# MATRIX_SCH.net
KiCad netlist of a schematic drawn in Altium Designer
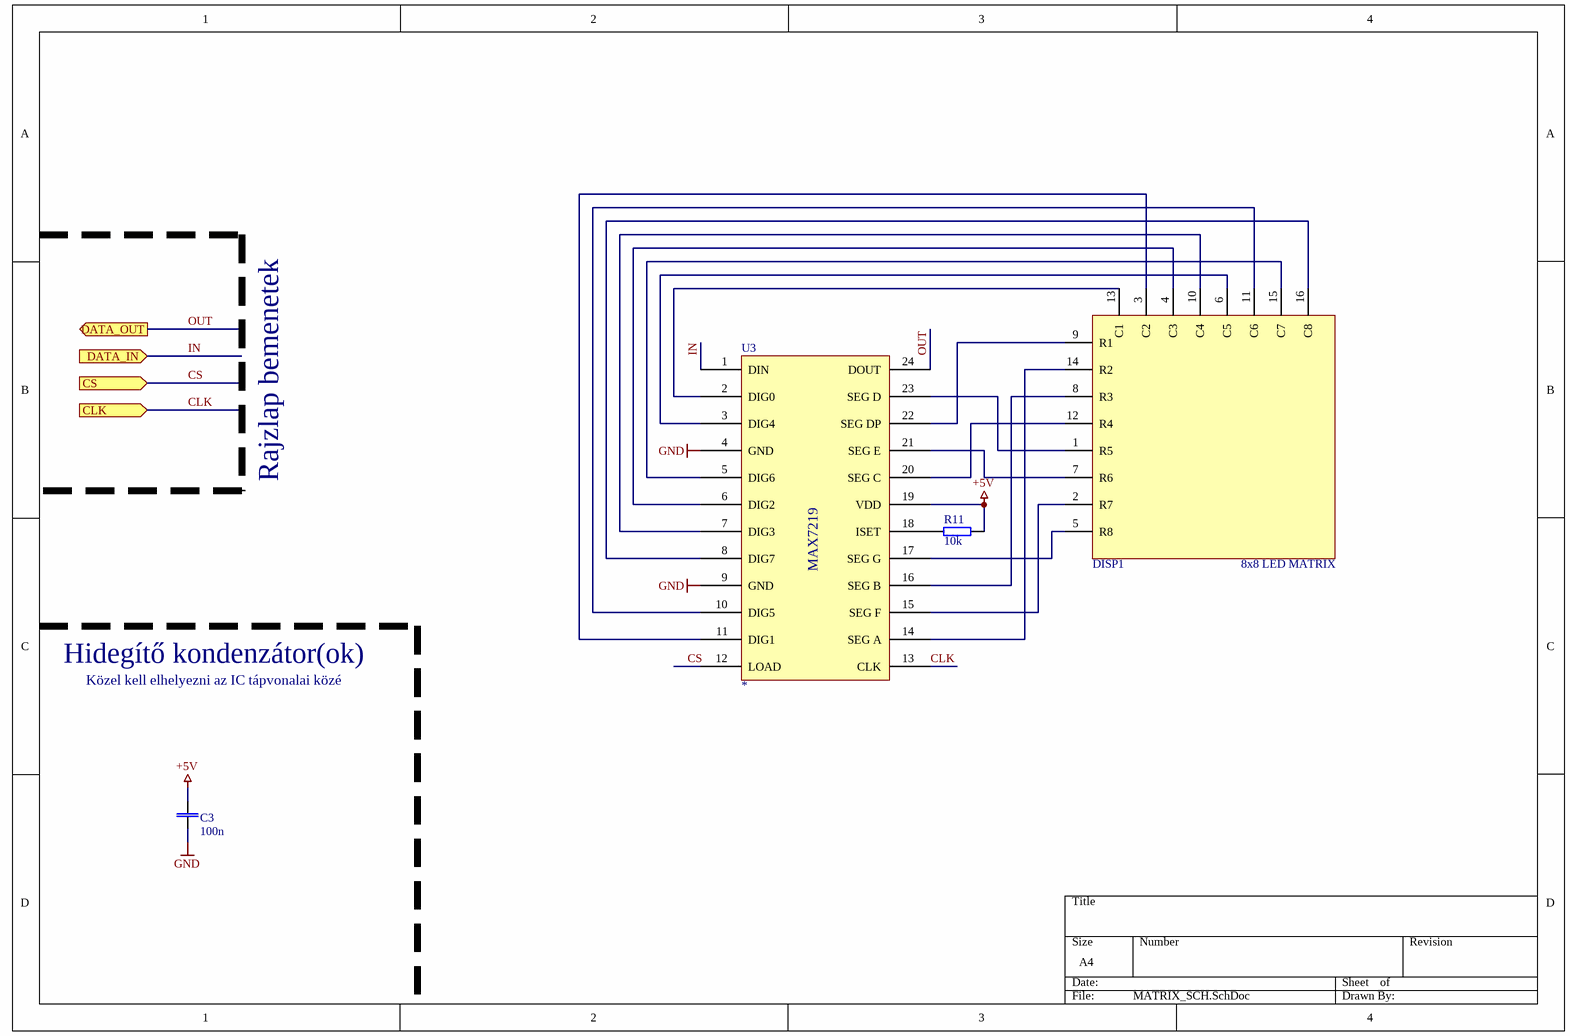
[diagram p0: MATRIX_SCH.SchDoc]

(export (version "E")
  (design (tool "Eeschema 10.0.6"))
  (components
    (comp (ref "C3")
      (value "100n")
      (footprint "CAP 0805")
      (description "NON POLARIZED CAPACITOR")
      (libsource (lib "SCH_LIB") (part "CAP"))
    )
    (comp (ref "DISP1")
      (value "8x8 LED MATRIX")
      (footprint "8x8_32mm_LED_MATRIX")
      (description "8x8 LED Matrix display")
      (libsource (lib "SCH_LIB") (part "8x8_LED_MATRIX"))
    )
    (comp (ref "R11")
      (value "10k")
      (footprint "RES 0805")
      (description "RESISTOR")
      (libsource (lib "SCH_LIB") (part "RES"))
    )
    (comp (ref "U3")
      (value "*")
      (footprint "SO24")
      (description "8X8 LED DRIVER IC")
      (libsource (lib "SCH_LIB") (part "MAX7219"))
    )
  )
  (nets
    (net (code "1") (name "+5V") (class "Default")
      (node (ref "C3") (pin "2") (pinfunction "2_2") (pintype "passive"))
      (node (ref "R11") (pin "2") (pinfunction "2_2") (pintype "passive"))
      (node (ref "U3") (pin "19") (pinfunction "VDD_19") (pintype "passive"))
    )
    (net (code "2") (name "/CLK") (class "Default")
      (node (ref "U3") (pin "13") (pinfunction "CLK_13") (pintype "passive"))
    )
    (net (code "3") (name "/CS") (class "Default")
      (node (ref "U3") (pin "12") (pinfunction "LOAD_12") (pintype "passive"))
    )
    (net (code "4") (name "/IN") (class "Default")
      (node (ref "U3") (pin "1") (pinfunction "DIN_1") (pintype "passive"))
    )
    (net (code "5") (name "/OUT") (class "Default")
      (node (ref "U3") (pin "24") (pinfunction "DOUT_24") (pintype "passive"))
    )
    (net (code "6") (name "GND") (class "Default")
      (node (ref "C3") (pin "1") (pinfunction "1_1") (pintype "passive"))
      (node (ref "U3") (pin "4") (pinfunction "GND_4") (pintype "passive"))
      (node (ref "U3") (pin "9") (pinfunction "GND_9") (pintype "passive"))
    )
    (net (code "7") (name "Net-(DISP1-C1)") (class "Default")
      (node (ref "DISP1") (pin "13") (pinfunction "C1_13") (pintype "passive"))
      (node (ref "U3") (pin "2") (pinfunction "DIG0_2") (pintype "passive"))
    )
    (net (code "8") (name "Net-(DISP1-C2)") (class "Default")
      (node (ref "DISP1") (pin "3") (pinfunction "C2_3") (pintype "passive"))
      (node (ref "U3") (pin "11") (pinfunction "DIG1_11") (pintype "passive"))
    )
    (net (code "9") (name "Net-(DISP1-C3)") (class "Default")
      (node (ref "DISP1") (pin "4") (pinfunction "C3_4") (pintype "passive"))
      (node (ref "U3") (pin "6") (pinfunction "DIG2_6") (pintype "passive"))
    )
    (net (code "10") (name "Net-(DISP1-C4)") (class "Default")
      (node (ref "DISP1") (pin "10") (pinfunction "C4_10") (pintype "passive"))
      (node (ref "U3") (pin "7") (pinfunction "DIG3_7") (pintype "passive"))
    )
    (net (code "11") (name "Net-(DISP1-C5)") (class "Default")
      (node (ref "DISP1") (pin "6") (pinfunction "C5_6") (pintype "passive"))
      (node (ref "U3") (pin "3") (pinfunction "DIG4_3") (pintype "passive"))
    )
    (net (code "12") (name "Net-(DISP1-C6)") (class "Default")
      (node (ref "DISP1") (pin "11") (pinfunction "C6_11") (pintype "passive"))
      (node (ref "U3") (pin "10") (pinfunction "DIG5_10") (pintype "passive"))
    )
    (net (code "13") (name "Net-(DISP1-C7)") (class "Default")
      (node (ref "DISP1") (pin "15") (pinfunction "C7_15") (pintype "passive"))
      (node (ref "U3") (pin "5") (pinfunction "DIG6_5") (pintype "passive"))
    )
    (net (code "14") (name "Net-(DISP1-C8)") (class "Default")
      (node (ref "DISP1") (pin "16") (pinfunction "C8_16") (pintype "passive"))
      (node (ref "U3") (pin "8") (pinfunction "DIG7_8") (pintype "passive"))
    )
    (net (code "15") (name "Net-(DISP1-R1)") (class "Default")
      (node (ref "DISP1") (pin "9") (pinfunction "R1_9") (pintype "passive"))
      (node (ref "U3") (pin "22") (pinfunction "SEG_DP_22") (pintype "passive"))
    )
    (net (code "16") (name "Net-(DISP1-R2)") (class "Default")
      (node (ref "DISP1") (pin "14") (pinfunction "R2_14") (pintype "passive"))
      (node (ref "U3") (pin "14") (pinfunction "SEG_A_14") (pintype "passive"))
    )
    (net (code "17") (name "Net-(DISP1-R3)") (class "Default")
      (node (ref "DISP1") (pin "8") (pinfunction "R3_8") (pintype "passive"))
      (node (ref "U3") (pin "16") (pinfunction "SEG_B_16") (pintype "passive"))
    )
    (net (code "18") (name "Net-(DISP1-R4)") (class "Default")
      (node (ref "DISP1") (pin "12") (pinfunction "R4_12") (pintype "passive"))
      (node (ref "U3") (pin "20") (pinfunction "SEG_C_20") (pintype "passive"))
    )
    (net (code "19") (name "Net-(DISP1-R5)") (class "Default")
      (node (ref "DISP1") (pin "1") (pinfunction "R5_1") (pintype "passive"))
      (node (ref "U3") (pin "23") (pinfunction "SEG_D_23") (pintype "passive"))
    )
    (net (code "20") (name "Net-(DISP1-R6)") (class "Default")
      (node (ref "DISP1") (pin "7") (pinfunction "R6_7") (pintype "passive"))
      (node (ref "U3") (pin "21") (pinfunction "SEG_E_21") (pintype "passive"))
    )
    (net (code "21") (name "Net-(DISP1-R7)") (class "Default")
      (node (ref "DISP1") (pin "2") (pinfunction "R7_2") (pintype "passive"))
      (node (ref "U3") (pin "15") (pinfunction "SEG_F_15") (pintype "passive"))
    )
    (net (code "22") (name "Net-(DISP1-R8)") (class "Default")
      (node (ref "DISP1") (pin "5") (pinfunction "R8_5") (pintype "passive"))
      (node (ref "U3") (pin "17") (pinfunction "SEG_G_17") (pintype "passive"))
    )
    (net (code "23") (name "Net-(U3-ISET)") (class "Default")
      (node (ref "R11") (pin "1") (pinfunction "1_1") (pintype "passive"))
      (node (ref "U3") (pin "18") (pinfunction "ISET_18") (pintype "passive"))
    )
  )
)
